# Mabee_DAC_GP8413_V1_1.net
KiCad netlist of a schematic drawn in EAGLE
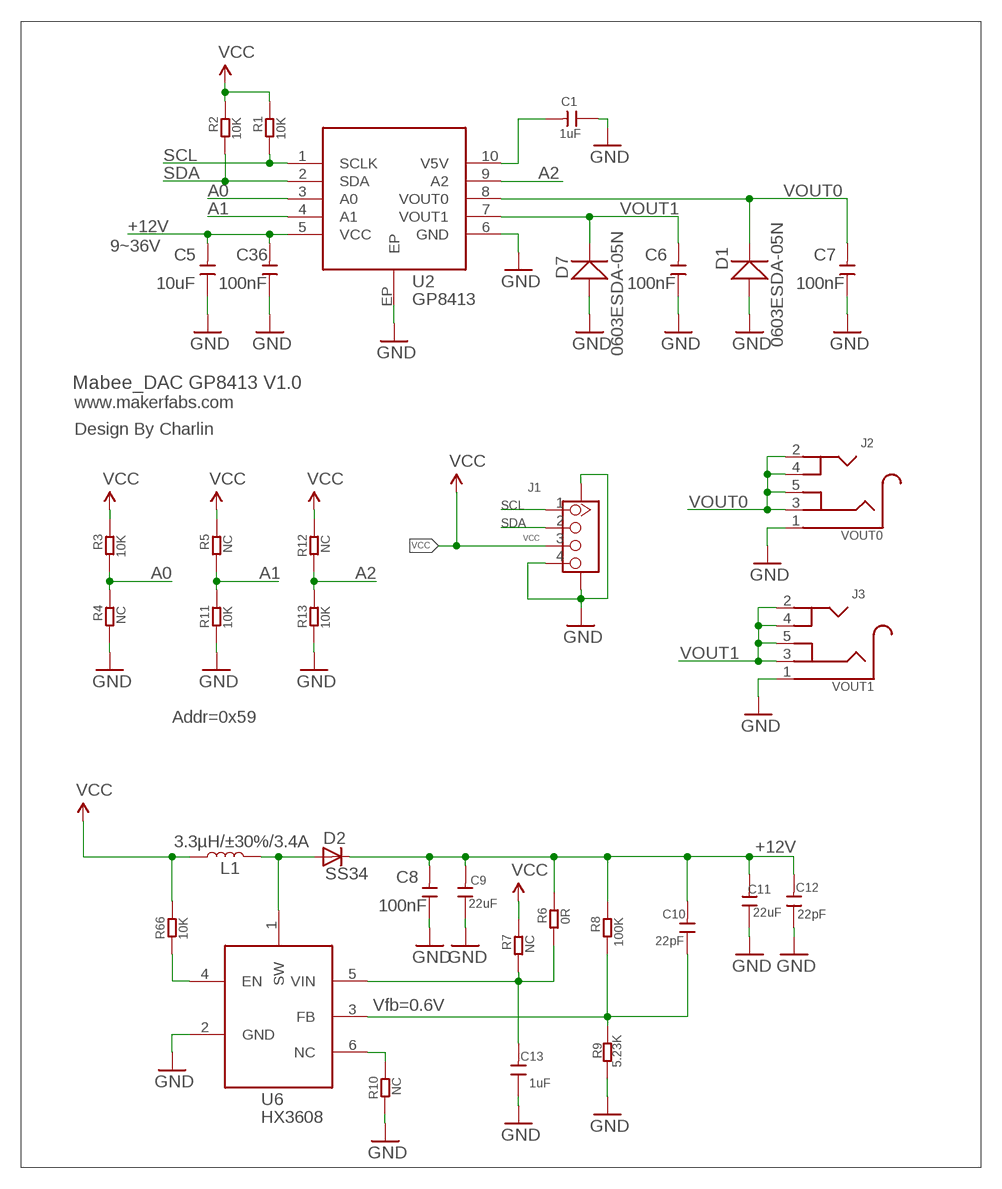
[diagram p0: schematic, sheet 1]

(export (version "E")
  (design (tool "Eeschema 10.0.6"))
  (components
    (comp (ref "C1")
      (value "1uF")
      (footprint "eagle-import:0603")
      (libsource (lib "eagle-import") (part "C-0603"))
    )
    (comp (ref "C5")
      (value "10uF")
      (footprint "eagle-import:0603")
      (libsource (lib "eagle-import") (part "C-0603"))
    )
    (comp (ref "C6")
      (value "100nF")
      (footprint "eagle-import:0603")
      (libsource (lib "eagle-import") (part "C-0603"))
    )
    (comp (ref "C7")
      (value "100nF")
      (footprint "eagle-import:0603")
      (libsource (lib "eagle-import") (part "C-0603"))
    )
    (comp (ref "C8")
      (value "100nF")
      (footprint "eagle-import:0603")
      (libsource (lib "eagle-import") (part "C-0603"))
    )
    (comp (ref "C9")
      (value "22uF")
      (footprint "eagle-import:DISCRETE_C0805")
      (libsource (lib "eagle-import") (part "DISCRETE_C-0805"))
    )
    (comp (ref "C10")
      (value "22pF")
      (footprint "eagle-import:0603")
      (libsource (lib "eagle-import") (part "C-0603"))
    )
    (comp (ref "C11")
      (value "22uF")
      (footprint "eagle-import:DISCRETE_C0805")
      (libsource (lib "eagle-import") (part "DISCRETE_C-0805"))
    )
    (comp (ref "C12")
      (value "22pF")
      (footprint "eagle-import:0603")
      (libsource (lib "eagle-import") (part "C-0603"))
    )
    (comp (ref "C13")
      (value "1uF")
      (footprint "eagle-import:0603")
      (libsource (lib "eagle-import") (part "C-0603"))
    )
    (comp (ref "C36")
      (value "100nF")
      (footprint "eagle-import:0603")
      (libsource (lib "eagle-import") (part "C-0603"))
    )
    (comp (ref "D1")
      (value "0603ESDA-05N")
      (footprint "eagle-import:DISCRETE_SOD523")
      (libsource (lib "eagle-import") (part "DISCRETE_D0603"))
    )
    (comp (ref "D2")
      (value "SS34")
      (footprint "eagle-import:DO-214AC")
      (libsource (lib "eagle-import") (part "DIODE-DO-214AC"))
    )
    (comp (ref "D7")
      (value "0603ESDA-05N")
      (footprint "eagle-import:DISCRETE_SOD523")
      (libsource (lib "eagle-import") (part "DISCRETE_D0603"))
    )
    (comp (ref "J1")
      (value "GROVE-CONNECTOR-SMD'90D'")
      (footprint "eagle-import:HW4-SMD-2.0-90D")
      (libsource (lib "eagle-import") (part "GROVE-CONNECTOR-SMD'90D'"))
    )
    (comp (ref "L1")
      (value "3.3µH/±30%/3.4A")
      (footprint "eagle-import:CR54")
      (libsource (lib "eagle-import") (part "INDUCTOR-CR54-3.3UH"))
    )
    (comp (ref "R1")
      (value "10K")
      (footprint "eagle-import:R0603")
      (libsource (lib "eagle-import") (part "R-0603"))
    )
    (comp (ref "R2")
      (value "10K")
      (footprint "eagle-import:R0603")
      (libsource (lib "eagle-import") (part "R-0603"))
    )
    (comp (ref "R3")
      (value "10K")
      (footprint "eagle-import:R0603")
      (libsource (lib "eagle-import") (part "R-0603"))
    )
    (comp (ref "R4")
      (value "NC")
      (footprint "eagle-import:R0603")
      (libsource (lib "eagle-import") (part "R-0603"))
    )
    (comp (ref "R5")
      (value "NC")
      (footprint "eagle-import:R0603")
      (libsource (lib "eagle-import") (part "R-0603"))
    )
    (comp (ref "R6")
      (value "0R")
      (footprint "eagle-import:R0603")
      (libsource (lib "eagle-import") (part "R-0603"))
    )
    (comp (ref "R7")
      (value "NC")
      (footprint "eagle-import:R0603")
      (libsource (lib "eagle-import") (part "R-0603"))
    )
    (comp (ref "R8")
      (value "100K")
      (footprint "eagle-import:R0603")
      (libsource (lib "eagle-import") (part "R-0603"))
    )
    (comp (ref "R9")
      (value "5.23K")
      (footprint "eagle-import:R0603")
      (libsource (lib "eagle-import") (part "R-0603"))
    )
    (comp (ref "R10")
      (value "NC")
      (footprint "eagle-import:R0603")
      (libsource (lib "eagle-import") (part "R-0603"))
    )
    (comp (ref "R11")
      (value "10K")
      (footprint "eagle-import:R0603")
      (libsource (lib "eagle-import") (part "R-0603"))
    )
    (comp (ref "R12")
      (value "NC")
      (footprint "eagle-import:R0603")
      (libsource (lib "eagle-import") (part "R-0603"))
    )
    (comp (ref "R13")
      (value "10K")
      (footprint "eagle-import:R0603")
      (libsource (lib "eagle-import") (part "R-0603"))
    )
    (comp (ref "R66")
      (value "10K")
      (footprint "eagle-import:R0603")
      (libsource (lib "eagle-import") (part "R-0603"))
    )
    (comp (ref "U2")
      (value "GP8413")
      (footprint "eagle-import:ESOP-10-EP-150MIL")
      (libsource (lib "eagle-import") (part "GP8413"))
    )
    (comp (ref "U6")
      (value "HX3608")
      (footprint "eagle-import:SOT-23-6")
      (libsource (lib "eagle-import") (part "HX3608"))
    )
    (comp (ref "VOUT0")
      (value "J2")
      (footprint "eagle-import:4UCONN_19269")
      (libsource (lib "eagle-import") (part "AUDIO_3.5MMJACK"))
    )
    (comp (ref "VOUT1")
      (value "J3")
      (footprint "eagle-import:4UCONN_19269")
      (libsource (lib "eagle-import") (part "AUDIO_3.5MMJACK"))
    )
  )
  (nets
    (net (code "1") (name "/+12V") (class "Default")
      (node (ref "C10") (pin "2") (pinfunction "2_2") (pintype "passive"))
      (node (ref "C11") (pin "2") (pinfunction "2_2") (pintype "passive"))
      (node (ref "C12") (pin "2") (pinfunction "2_2") (pintype "passive"))
      (node (ref "C36") (pin "2") (pinfunction "2_2") (pintype "passive"))
      (node (ref "C5") (pin "2") (pinfunction "2_2") (pintype "passive"))
      (node (ref "C8") (pin "2") (pinfunction "2_2") (pintype "passive"))
      (node (ref "C9") (pin "2") (pinfunction "2_2") (pintype "passive"))
      (node (ref "D2") (pin "C") (pinfunction "C_C") (pintype "passive"))
      (node (ref "R6") (pin "2") (pinfunction "2_2") (pintype "passive"))
      (node (ref "R8") (pin "2") (pinfunction "2_2") (pintype "passive"))
      (node (ref "U2") (pin "5") (pinfunction "VCC_5") (pintype "bidirectional"))
    )
    (net (code "2") (name "/A0") (class "Default")
      (node (ref "R3") (pin "1") (pinfunction "1_1") (pintype "passive"))
      (node (ref "R4") (pin "2") (pinfunction "2_2") (pintype "passive"))
      (node (ref "U2") (pin "3") (pinfunction "A0_3") (pintype "bidirectional"))
    )
    (net (code "3") (name "/A1") (class "Default")
      (node (ref "R11") (pin "2") (pinfunction "2_2") (pintype "passive"))
      (node (ref "R5") (pin "1") (pinfunction "1_1") (pintype "passive"))
      (node (ref "U2") (pin "4") (pinfunction "A1_4") (pintype "bidirectional"))
    )
    (net (code "4") (name "/A2") (class "Default")
      (node (ref "R12") (pin "1") (pinfunction "1_1") (pintype "passive"))
      (node (ref "R13") (pin "2") (pinfunction "2_2") (pintype "passive"))
      (node (ref "U2") (pin "9") (pinfunction "A2_9") (pintype "bidirectional"))
    )
    (net (code "5") (name "/SCL") (class "Default")
      (node (ref "J1") (pin "1") (pinfunction "1_1") (pintype "bidirectional"))
      (node (ref "R1") (pin "1") (pinfunction "1_1") (pintype "passive"))
      (node (ref "U2") (pin "1") (pinfunction "SCLK_1") (pintype "bidirectional"))
    )
    (net (code "6") (name "/SDA") (class "Default")
      (node (ref "J1") (pin "2") (pinfunction "2_2") (pintype "bidirectional"))
      (node (ref "R2") (pin "1") (pinfunction "1_1") (pintype "passive"))
      (node (ref "U2") (pin "2") (pinfunction "SDA_2") (pintype "bidirectional"))
    )
    (net (code "7") (name "/VOUT0") (class "Default")
      (node (ref "C7") (pin "2") (pinfunction "2_2") (pintype "passive"))
      (node (ref "D1") (pin "-") (pinfunction "-_-") (pintype "passive"))
      (node (ref "U2") (pin "8") (pinfunction "VOUT0_8") (pintype "bidirectional"))
      (node (ref "VOUT0") (pin "2") (pinfunction "P$5_2") (pintype "bidirectional"))
      (node (ref "VOUT0") (pin "3") (pinfunction "P$2_3") (pintype "bidirectional"))
      (node (ref "VOUT0") (pin "4") (pinfunction "P$4_4") (pintype "bidirectional"))
      (node (ref "VOUT0") (pin "5") (pinfunction "P$3_5") (pintype "bidirectional"))
    )
    (net (code "8") (name "/VOUT1") (class "Default")
      (node (ref "C6") (pin "2") (pinfunction "2_2") (pintype "passive"))
      (node (ref "D7") (pin "-") (pinfunction "-_-") (pintype "passive"))
      (node (ref "U2") (pin "7") (pinfunction "VOUT1_7") (pintype "bidirectional"))
      (node (ref "VOUT1") (pin "2") (pinfunction "P$5_2") (pintype "bidirectional"))
      (node (ref "VOUT1") (pin "3") (pinfunction "P$2_3") (pintype "bidirectional"))
      (node (ref "VOUT1") (pin "4") (pinfunction "P$4_4") (pintype "bidirectional"))
      (node (ref "VOUT1") (pin "5") (pinfunction "P$3_5") (pintype "bidirectional"))
    )
    (net (code "9") (name "GND") (class "Default")
      (node (ref "C1") (pin "1") (pinfunction "1_1") (pintype "passive"))
      (node (ref "C11") (pin "1") (pinfunction "1_1") (pintype "passive"))
      (node (ref "C12") (pin "1") (pinfunction "1_1") (pintype "passive"))
      (node (ref "C13") (pin "1") (pinfunction "1_1") (pintype "passive"))
      (node (ref "C36") (pin "1") (pinfunction "1_1") (pintype "passive"))
      (node (ref "C5") (pin "1") (pinfunction "1_1") (pintype "passive"))
      (node (ref "C6") (pin "1") (pinfunction "1_1") (pintype "passive"))
      (node (ref "C7") (pin "1") (pinfunction "1_1") (pintype "passive"))
      (node (ref "C8") (pin "1") (pinfunction "1_1") (pintype "passive"))
      (node (ref "C9") (pin "1") (pinfunction "1_1") (pintype "passive"))
      (node (ref "D1") (pin "+") (pinfunction "+_+") (pintype "passive"))
      (node (ref "D7") (pin "+") (pinfunction "+_+") (pintype "passive"))
      (node (ref "J1") (pin "4") (pinfunction "4_4") (pintype "bidirectional"))
      (node (ref "J1") (pin "SS1") (pinfunction "SS1_SS1") (pintype "bidirectional"))
      (node (ref "J1") (pin "SS2") (pinfunction "SS2_SS2") (pintype "bidirectional"))
      (node (ref "R10") (pin "1") (pinfunction "1_1") (pintype "passive"))
      (node (ref "R11") (pin "1") (pinfunction "1_1") (pintype "passive"))
      (node (ref "R13") (pin "1") (pinfunction "1_1") (pintype "passive"))
      (node (ref "R4") (pin "1") (pinfunction "1_1") (pintype "passive"))
      (node (ref "R9") (pin "1") (pinfunction "1_1") (pintype "passive"))
      (node (ref "U2") (pin "6") (pinfunction "GND_6") (pintype "bidirectional"))
      (node (ref "U2") (pin "EP") (pinfunction "EP_EP") (pintype "bidirectional"))
      (node (ref "U6") (pin "2") (pinfunction "GND_2") (pintype "bidirectional"))
      (node (ref "VOUT0") (pin "1") (pinfunction "P$1_1") (pintype "bidirectional"))
      (node (ref "VOUT1") (pin "1") (pinfunction "P$1_1") (pintype "bidirectional"))
    )
    (net (code "10") (name "Net-(L1-2)") (class "Default")
      (node (ref "D2") (pin "A") (pinfunction "A_A") (pintype "passive"))
      (node (ref "L1") (pin "P$2") (pinfunction "2_P$2") (pintype "passive"))
      (node (ref "U6") (pin "1") (pinfunction "SW_1") (pintype "bidirectional"))
    )
    (net (code "11") (name "Net-(U2-V5V)") (class "Default")
      (node (ref "C1") (pin "2") (pinfunction "2_2") (pintype "passive"))
      (node (ref "U2") (pin "10") (pinfunction "V5V_10") (pintype "bidirectional"))
    )
    (net (code "12") (name "Net-(U6-EN)") (class "Default")
      (node (ref "R66") (pin "1") (pinfunction "1_1") (pintype "passive"))
      (node (ref "U6") (pin "4") (pinfunction "EN_4") (pintype "bidirectional"))
    )
    (net (code "13") (name "Net-(U6-FB)") (class "Default")
      (node (ref "C10") (pin "1") (pinfunction "1_1") (pintype "passive"))
      (node (ref "R8") (pin "1") (pinfunction "1_1") (pintype "passive"))
      (node (ref "R9") (pin "2") (pinfunction "2_2") (pintype "passive"))
      (node (ref "U6") (pin "3") (pinfunction "FB_3") (pintype "bidirectional"))
    )
    (net (code "14") (name "Net-(U6-NC)") (class "Default")
      (node (ref "R10") (pin "2") (pinfunction "2_2") (pintype "passive"))
      (node (ref "U6") (pin "6") (pinfunction "NC_6") (pintype "bidirectional"))
    )
    (net (code "15") (name "Net-(U6-VIN)") (class "Default")
      (node (ref "C13") (pin "2") (pinfunction "2_2") (pintype "passive"))
      (node (ref "R6") (pin "1") (pinfunction "1_1") (pintype "passive"))
      (node (ref "R7") (pin "1") (pinfunction "1_1") (pintype "passive"))
      (node (ref "U6") (pin "5") (pinfunction "VIN_5") (pintype "bidirectional"))
    )
    (net (code "16") (name "VCC") (class "Default")
      (node (ref "J1") (pin "3") (pinfunction "3_3") (pintype "bidirectional"))
      (node (ref "L1") (pin "P$1") (pinfunction "1_P$1") (pintype "passive"))
      (node (ref "R1") (pin "2") (pinfunction "2_2") (pintype "passive"))
      (node (ref "R12") (pin "2") (pinfunction "2_2") (pintype "passive"))
      (node (ref "R2") (pin "2") (pinfunction "2_2") (pintype "passive"))
      (node (ref "R3") (pin "2") (pinfunction "2_2") (pintype "passive"))
      (node (ref "R5") (pin "2") (pinfunction "2_2") (pintype "passive"))
      (node (ref "R66") (pin "2") (pinfunction "2_2") (pintype "passive"))
      (node (ref "R7") (pin "2") (pinfunction "2_2") (pintype "passive"))
    )
  )
)
